# amplifier.net
KiCad netlist of a schematic drawn in EAGLE
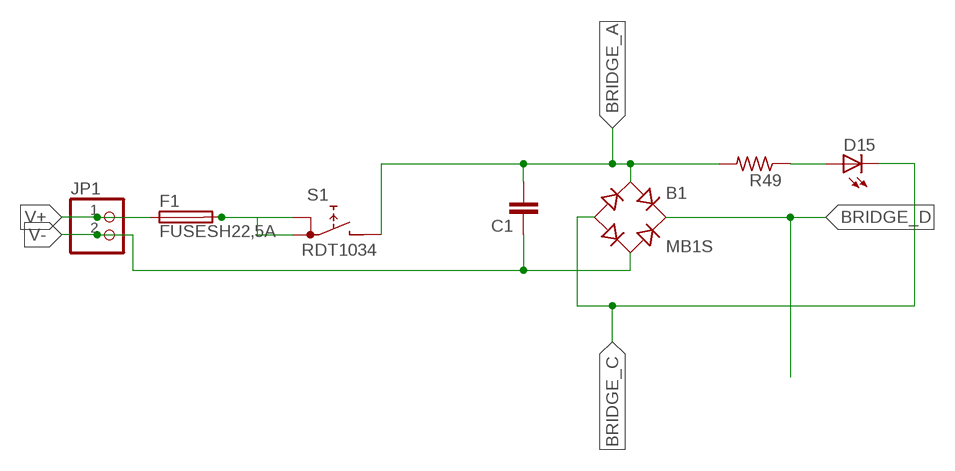
[diagram p0: schematic, sheet 1]

(export (version "E")
  (design (tool "Eeschema 10.0.6"))
  (components
    (comp (ref "B1")
      (value "MB1S")
      (footprint "eagle-import:SOIC-4")
      (libsource (lib "eagle-import") (part "MBS1"))
    )
    (comp (ref "C1")
      (value "C-EUC0603")
      (footprint "eagle-import:C0603")
      (libsource (lib "eagle-import") (part "C-EUC0603"))
    )
    (comp (ref "D15")
      (value "LEDCHIP-LED0603")
      (footprint "eagle-import:CHIP-LED0603")
      (libsource (lib "eagle-import") (part "LEDCHIP-LED0603"))
    )
    (comp (ref "F1")
      (value "FUSESH22,5A")
      (footprint "eagle-import:SH22,5A")
      (libsource (lib "eagle-import") (part "FUSESH22,5A"))
    )
    (comp (ref "JP1")
      (value "PINHD-1X2")
      (footprint "eagle-import:1X02")
      (libsource (lib "eagle-import") (part "PINHD-1X2"))
    )
    (comp (ref "R49")
      (value "R-US_R0603")
      (footprint "eagle-import:R0603")
      (libsource (lib "eagle-import") (part "R-US_R0603"))
    )
    (comp (ref "S1")
      (value "RDT1034")
      (footprint "eagle-import:RDT1034")
      (libsource (lib "eagle-import") (part "RDT1034"))
    )
  )
  (nets
    (net (code "1") (name "BRIDGE_A") (class "Default")
      (node (ref "B1") (pin "~1") (pinfunction "AC1_~1") (pintype "passive"))
      (node (ref "C1") (pin "2") (pinfunction "2_2") (pintype "passive"))
      (node (ref "R49") (pin "2") (pinfunction "2_2") (pintype "passive"))
      (node (ref "S1") (pin "B") (pinfunction "B_B") (pintype "passive"))
    )
    (net (code "2") (name "BRIDGE_C") (class "Default")
      (node (ref "B1") (pin "-") (pinfunction "-_-") (pintype "passive"))
      (node (ref "D15") (pin "C") (pinfunction "C_C") (pintype "passive"))
    )
    (net (code "3") (name "BRIDGE_D") (class "Default")
      (node (ref "B1") (pin "+") (pinfunction "+_+") (pintype "passive"))
    )
    (net (code "4") (name "Net-(D15-PadA)") (class "Default")
      (node (ref "D15") (pin "A") (pinfunction "A_A") (pintype "passive"))
      (node (ref "R49") (pin "1") (pinfunction "1_1") (pintype "passive"))
    )
    (net (code "5") (name "Net-(F1-Pad2)") (class "Default")
      (node (ref "F1") (pin "2") (pinfunction "2_2") (pintype "passive"))
      (node (ref "S1") (pin "A") (pinfunction "A_A") (pintype "passive"))
      (node (ref "S1") (pin "A1") (pinfunction "A1_A1") (pintype "passive"))
    )
    (net (code "6") (name "V+") (class "Default")
      (node (ref "F1") (pin "1") (pinfunction "1_1") (pintype "passive"))
      (node (ref "JP1") (pin "1") (pinfunction "1_1") (pintype "passive"))
    )
    (net (code "7") (name "V-") (class "Default")
      (node (ref "B1") (pin "~2") (pinfunction "AC2_~2") (pintype "passive"))
      (node (ref "C1") (pin "1") (pinfunction "1_1") (pintype "passive"))
      (node (ref "JP1") (pin "2") (pinfunction "2_2") (pintype "passive"))
    )
  )
)
